# PWMDriver.net
KiCad netlist of a schematic drawn in Altium Designer
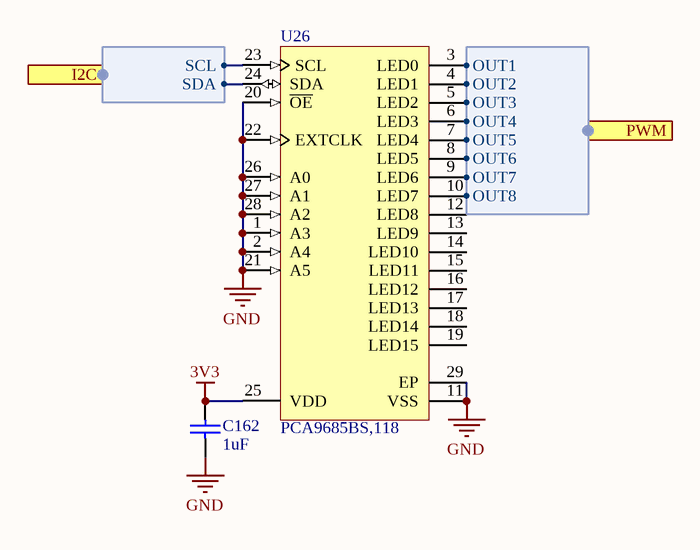
[diagram p0: PWMDriver.SchDoc]

(export (version "E")
  (design (tool "Eeschema 10.0.6"))
  (components
    (comp (ref "C162")
      (value "1uF")
      (footprint "C0402[1005X55]")
      (description "1uF 6.3V 10% 0402 (1005 Metric)")
      (fields (field (name "PARTNUMBER") "GRM155R70J105KA12D") (field (name "MANUFACTURER") "Murata"))
      (libsource (lib "Capacitors") (part "CAP_1uF_6.3V_0402_10%"))
    )
    (comp (ref "U26")
      (value "PCA9685BS,118")
      (footprint "VQFN-28")
      (description "IC LED DRVR LIN DIM 25MA 28HVQFN")
      (fields (field (name "MANUFACTURER") "NXP"))
      (libsource (lib "ICs") (part "PCA9685BS,118"))
    )
  )
  (nets
    (net (code "3") (name "/OUT1") (class "Default")
      (node (ref "U26") (pin "3") (pinfunction "LED0_3") (pintype "tri_state"))
    )
    (net (code "4") (name "/OUT2") (class "Default")
      (node (ref "U26") (pin "4") (pinfunction "LED1_4") (pintype "tri_state"))
    )
    (net (code "5") (name "/OUT3") (class "Default")
      (node (ref "U26") (pin "5") (pinfunction "LED2_5") (pintype "tri_state"))
    )
    (net (code "6") (name "/OUT4") (class "Default")
      (node (ref "U26") (pin "6") (pinfunction "LED3_6") (pintype "tri_state"))
    )
    (net (code "7") (name "/OUT5") (class "Default")
      (node (ref "U26") (pin "7") (pinfunction "LED4_7") (pintype "tri_state"))
    )
    (net (code "8") (name "/OUT6") (class "Default")
      (node (ref "U26") (pin "8") (pinfunction "LED5_8") (pintype "tri_state"))
    )
    (net (code "9") (name "/OUT7") (class "Default")
      (node (ref "U26") (pin "9") (pinfunction "LED6_9") (pintype "tri_state"))
    )
    (net (code "10") (name "/OUT8") (class "Default")
      (node (ref "U26") (pin "10") (pinfunction "LED7_10") (pintype "tri_state"))
    )
    (net (code "11") (name "/SCL") (class "Default")
      (node (ref "U26") (pin "23") (pinfunction "SCL_23") (pintype "input"))
    )
    (net (code "12") (name "/SDA") (class "Default")
      (node (ref "U26") (pin "24") (pinfunction "SDA_24") (pintype "bidirectional"))
    )
    (net (code "15") (name "3V3") (class "Default")
      (node (ref "C162") (pin "2") (pinfunction "2_2") (pintype "passive"))
      (node (ref "U26") (pin "25") (pinfunction "VDD_25") (pintype "power_in"))
    )
    (net (code "16") (name "GND") (class "Default")
      (node (ref "C162") (pin "1") (pinfunction "1_1") (pintype "passive"))
      (node (ref "U26") (pin "1") (pinfunction "A3_1") (pintype "input"))
      (node (ref "U26") (pin "11") (pinfunction "VSS_11") (pintype "power_in"))
      (node (ref "U26") (pin "2") (pinfunction "A4_2") (pintype "input"))
      (node (ref "U26") (pin "20") (pinfunction "~{OE}_20") (pintype "input"))
      (node (ref "U26") (pin "21") (pinfunction "A5_21") (pintype "input"))
      (node (ref "U26") (pin "22") (pinfunction "EXTCLK_22") (pintype "input"))
      (node (ref "U26") (pin "26") (pinfunction "A0_26") (pintype "input"))
      (node (ref "U26") (pin "27") (pinfunction "A1_27") (pintype "input"))
      (node (ref "U26") (pin "28") (pinfunction "A2_28") (pintype "input"))
      (node (ref "U26") (pin "29") (pinfunction "EP_29") (pintype "power_in"))
    )
    (net (code "17") (name "unconnected-(U26-LED8-Pad12)") (class "Default")
      (node (ref "U26") (pin "12") (pinfunction "LED8_12") (pintype "tri_state"))
    )
    (net (code "18") (name "unconnected-(U26-LED9-Pad13)") (class "Default")
      (node (ref "U26") (pin "13") (pinfunction "LED9_13") (pintype "tri_state"))
    )
    (net (code "19") (name "unconnected-(U26-LED10-Pad14)") (class "Default")
      (node (ref "U26") (pin "14") (pinfunction "LED10_14") (pintype "tri_state"))
    )
    (net (code "20") (name "unconnected-(U26-LED11-Pad15)") (class "Default")
      (node (ref "U26") (pin "15") (pinfunction "LED11_15") (pintype "tri_state"))
    )
    (net (code "21") (name "unconnected-(U26-LED12-Pad16)") (class "Default")
      (node (ref "U26") (pin "16") (pinfunction "LED12_16") (pintype "tri_state"))
    )
    (net (code "22") (name "unconnected-(U26-LED13-Pad17)") (class "Default")
      (node (ref "U26") (pin "17") (pinfunction "LED13_17") (pintype "tri_state"))
    )
    (net (code "23") (name "unconnected-(U26-LED14-Pad18)") (class "Default")
      (node (ref "U26") (pin "18") (pinfunction "LED14_18") (pintype "tri_state"))
    )
    (net (code "24") (name "unconnected-(U26-LED15-Pad19)") (class "Default")
      (node (ref "U26") (pin "19") (pinfunction "LED15_19") (pintype "tri_state"))
    )
  )
)
